# AFE_Supply.net
KiCad netlist of a schematic drawn in Altium Designer
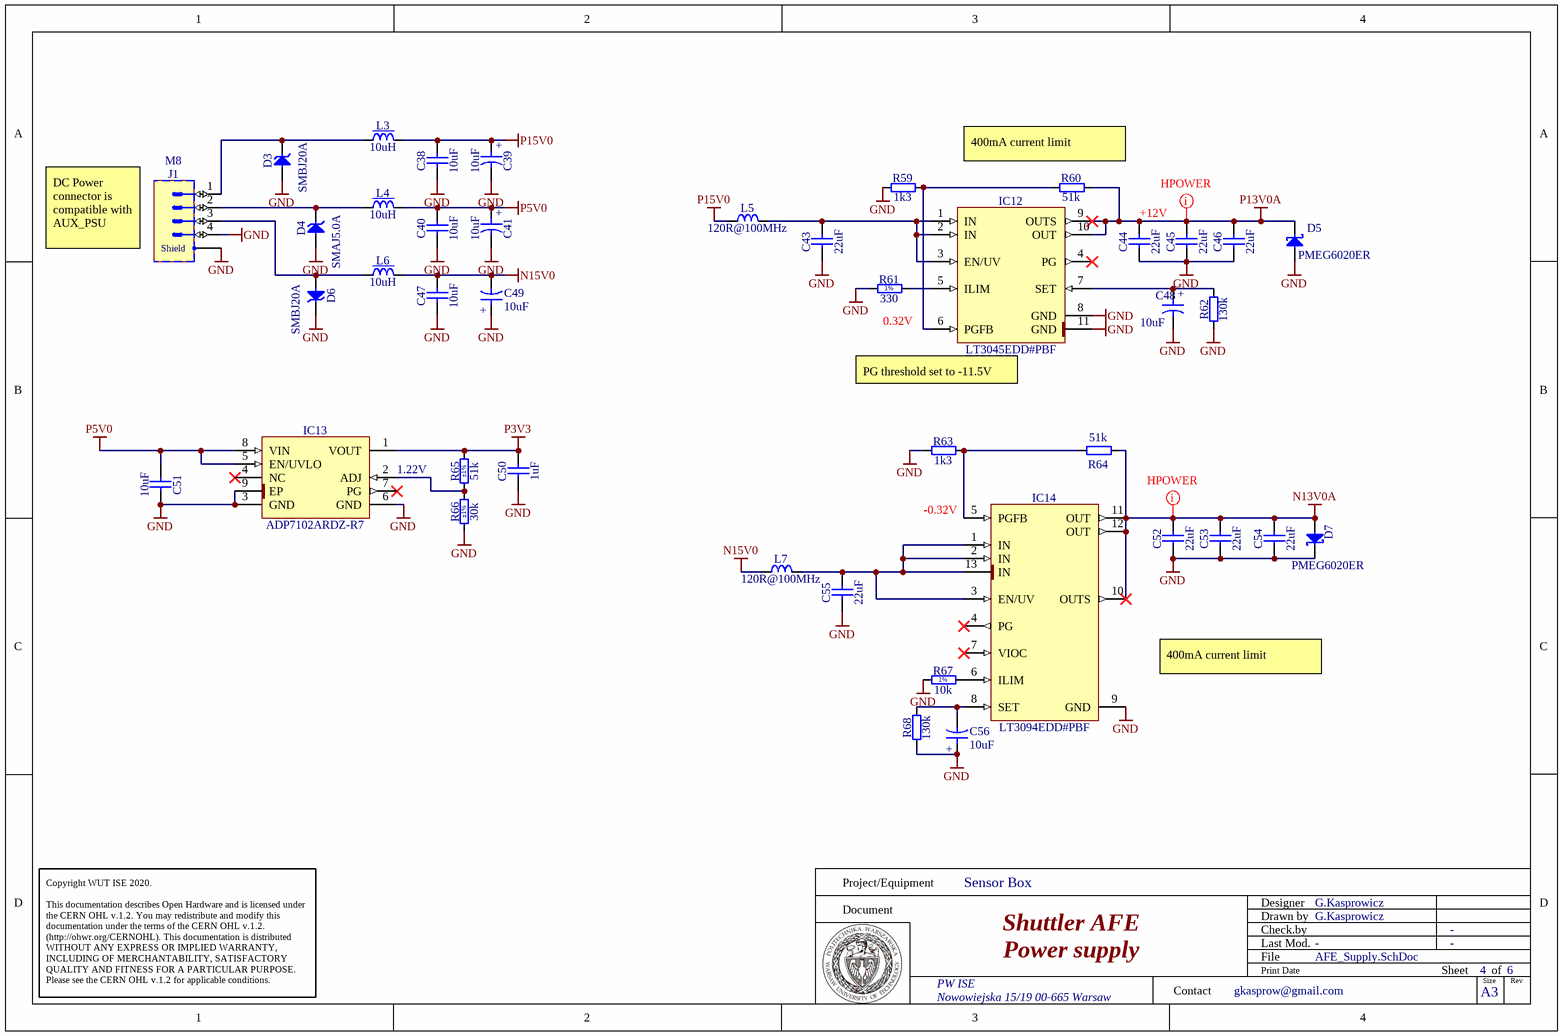
[diagram p0: AFE_Supply.SchDoc]

(export (version "E")
  (design (tool "Eeschema 10.0.6"))
  (components
    (comp (ref "C38")
      (value "10uF")
      (footprint "CAPC2012X95N")
      (description "Non-polarised capacitor")
      (fields
        (field (name "PART NUMBER") "CC0805_10UF_25V_10%_X5R")
        (field (name "VOLTAGE") "25V")
        (field (name "AUTHOR") "CERN DEM JLC")
      )
      (libsource (lib "Capacitors") (part "Capacitor - non polarized"))
    )
    (comp (ref "C39")
      (value "10uF")
      (footprint "CAPMP3216X180N")
      (description "Polarised capacitor")
      (fields
        (field (name "PART NUMBER") "CTE3216-18_10UF_16V_20%_AVX_TCJ")
        (field (name "VOLTAGE") "16V")
        (field (name "AUTHOR") "CERN DEM JLC")
      )
      (libsource (lib "Capacitors") (part "Capacitor - polarized"))
    )
    (comp (ref "C40")
      (value "10uF")
      (footprint "CAPC2012X95N")
      (description "Non-polarised capacitor")
      (fields
        (field (name "PART NUMBER") "CC0805_10UF_25V_10%_X5R")
        (field (name "VOLTAGE") "25V")
        (field (name "AUTHOR") "CERN DEM JLC")
      )
      (libsource (lib "Capacitors") (part "Capacitor - non polarized"))
    )
    (comp (ref "C41")
      (value "10uF")
      (footprint "CAPMP3216X180N")
      (description "Polarised capacitor")
      (fields
        (field (name "PART NUMBER") "CTE3216-18_10UF_16V_20%_AVX_TCJ")
        (field (name "VOLTAGE") "16V")
        (field (name "AUTHOR") "CERN DEM JLC")
      )
      (libsource (lib "Capacitors") (part "Capacitor - polarized"))
    )
    (comp (ref "C43")
      (value "22uF")
      (footprint "CAPC2012X135N")
      (description "Non-polarised capacitor")
      (fields
        (field (name "PART NUMBER") "CC0805_22UF_16V_10%_X5R")
        (field (name "VOLTAGE") "16V")
        (field (name "AUTHOR") "CERN DEM JLC")
      )
      (libsource (lib "Capacitors") (part "Capacitor - non polarized"))
    )
    (comp (ref "C44")
      (value "22uF")
      (footprint "CAPC2012X135N")
      (description "Non-polarised capacitor")
      (fields
        (field (name "PART NUMBER") "CC0805_22UF_16V_10%_X5R")
        (field (name "VOLTAGE") "16V")
        (field (name "AUTHOR") "CERN DEM JLC")
      )
      (libsource (lib "Capacitors") (part "Capacitor - non polarized"))
    )
    (comp (ref "C45")
      (value "22uF")
      (footprint "CAPC2012X135N")
      (description "Non-polarised capacitor")
      (fields
        (field (name "PART NUMBER") "CC0805_22UF_16V_10%_X5R")
        (field (name "VOLTAGE") "16V")
        (field (name "AUTHOR") "CERN DEM JLC")
      )
      (libsource (lib "Capacitors") (part "Capacitor - non polarized"))
    )
    (comp (ref "C46")
      (value "22uF")
      (footprint "CAPC2012X135N")
      (description "Non-polarised capacitor")
      (fields
        (field (name "PART NUMBER") "CC0805_22UF_16V_10%_X5R")
        (field (name "VOLTAGE") "16V")
        (field (name "AUTHOR") "CERN DEM JLC")
      )
      (libsource (lib "Capacitors") (part "Capacitor - non polarized"))
    )
    (comp (ref "C47")
      (value "10uF")
      (footprint "CAPC2012X95N")
      (description "Non-polarised capacitor")
      (fields
        (field (name "PART NUMBER") "CC0805_10UF_25V_10%_X5R")
        (field (name "VOLTAGE") "25V")
        (field (name "AUTHOR") "CERN DEM JLC")
      )
      (libsource (lib "Capacitors") (part "Capacitor - non polarized"))
    )
    (comp (ref "C48")
      (value "10uF")
      (footprint "CAPMP3216X180N")
      (description "Polarised capacitor")
      (fields
        (field (name "PART NUMBER") "CTE3216-18_10UF_16V_20%_AVX_TCJ")
        (field (name "VOLTAGE") "16V")
        (field (name "AUTHOR") "CERN DEM JLC")
      )
      (libsource (lib "Capacitors") (part "Capacitor - polarized"))
    )
    (comp (ref "C49")
      (value "10uF")
      (footprint "CAPMP3216X180N")
      (description "Polarised capacitor")
      (fields
        (field (name "PART NUMBER") "CTE3216-18_10UF_16V_20%_AVX_TCJ")
        (field (name "VOLTAGE") "16V")
        (field (name "AUTHOR") "CERN DEM JLC")
      )
      (libsource (lib "Capacitors") (part "Capacitor - polarized"))
    )
    (comp (ref "C50")
      (value "1uF")
      (footprint "CAPC1608X87N")
      (description "Non-polarised capacitor")
      (fields
        (field (name "PART NUMBER") "CC0603_1UF_25V_10%_X7R")
        (field (name "VOLTAGE") "25V")
        (field (name "AUTHOR") "CERN DEM JLC")
      )
      (libsource (lib "Capacitors") (part "Capacitor - non polarized"))
    )
    (comp (ref "C51")
      (value "10uF")
      (footprint "CAPC2012X135N")
      (description "Non-polarised capacitor")
      (fields
        (field (name "PART NUMBER") "CC0805_10UF_16V_10%_X5R")
        (field (name "VOLTAGE") "16V")
        (field (name "AUTHOR") "CERN DEM JLC")
      )
      (libsource (lib "Capacitors") (part "Capacitor - non polarized"))
    )
    (comp (ref "C52")
      (value "22uF")
      (footprint "CAPC2012X135N")
      (description "Non-polarised capacitor")
      (fields
        (field (name "PART NUMBER") "CC0805_22UF_16V_10%_X5R")
        (field (name "VOLTAGE") "16V")
        (field (name "AUTHOR") "CERN DEM JLC")
      )
      (libsource (lib "Capacitors") (part "Capacitor - non polarized"))
    )
    (comp (ref "C53")
      (value "22uF")
      (footprint "CAPC2012X135N")
      (description "Non-polarised capacitor")
      (fields
        (field (name "PART NUMBER") "CC0805_22UF_16V_10%_X5R")
        (field (name "VOLTAGE") "16V")
        (field (name "AUTHOR") "CERN DEM JLC")
      )
      (libsource (lib "Capacitors") (part "Capacitor - non polarized"))
    )
    (comp (ref "C54")
      (value "22uF")
      (footprint "CAPC2012X135N")
      (description "Non-polarised capacitor")
      (fields
        (field (name "PART NUMBER") "CC0805_22UF_16V_10%_X5R")
        (field (name "VOLTAGE") "16V")
        (field (name "AUTHOR") "CERN DEM JLC")
      )
      (libsource (lib "Capacitors") (part "Capacitor - non polarized"))
    )
    (comp (ref "C55")
      (value "22uF")
      (footprint "CAPC2012X135N")
      (description "Non-polarised capacitor")
      (fields
        (field (name "PART NUMBER") "CC0805_22UF_16V_10%_X5R")
        (field (name "VOLTAGE") "16V")
        (field (name "AUTHOR") "CERN DEM JLC")
      )
      (libsource (lib "Capacitors") (part "Capacitor - non polarized"))
    )
    (comp (ref "C56")
      (value "10uF")
      (footprint "CAPMP3216X180N")
      (description "Polarised capacitor")
      (fields
        (field (name "PART NUMBER") "CTE3216-18_10UF_16V_20%_AVX_TCJ")
        (field (name "VOLTAGE") "16V")
        (field (name "AUTHOR") "CERN DEM JLC")
      )
      (libsource (lib "Capacitors") (part "Capacitor - polarized"))
    )
    (comp (ref "D3")
      (value "SMBJ20A")
      (footprint "DIOM5336X265N")
      (description "Transient Voltage Suppressor Diode (Uni-Directional)")
      (fields
        (field (name "VOLTAGE") "20V")
        (field (name "POWER") "600W")
        (field (name "AUTHOR") "CERN DEM JLC")
      )
      (libsource (lib "ICs And Semiconductors") (part "Diode TVS Uni-Directional"))
    )
    (comp (ref "D4")
      (value "SMAJ5.0A")
      (footprint "DIOM5226X262N")
      (description "Transient Voltage Suppressor Diode (Uni-Directional)")
      (fields
        (field (name "VOLTAGE") "5V")
        (field (name "POWER") "400W")
        (field (name "AUTHOR") "CERN DEM MR")
      )
      (libsource (lib "ICs And Semiconductors") (part "Diode TVS Uni-Directional"))
    )
    (comp (ref "D5")
      (value "PMEG6020ER")
      (footprint "SODFL3517X110N")
      (description "Schottky Diode")
      (fields
        (field (name "VOLTAGE") "60V")
        (field (name "POWER") "2A")
        (field (name "AUTHOR") "CERN DEM JMW")
      )
      (libsource (lib "ICs And Semiconductors") (part "Diode Schottky"))
    )
    (comp (ref "D6")
      (value "SMBJ20A")
      (footprint "DIOM5336X265N")
      (description "Transient Voltage Suppressor Diode (Uni-Directional)")
      (fields
        (field (name "VOLTAGE") "20V")
        (field (name "POWER") "600W")
        (field (name "AUTHOR") "CERN DEM JLC")
      )
      (libsource (lib "ICs And Semiconductors") (part "Diode TVS Uni-Directional"))
    )
    (comp (ref "D7")
      (value "PMEG6020ER")
      (footprint "SODFL3517X110N")
      (description "Schottky Diode")
      (fields
        (field (name "VOLTAGE") "60V")
        (field (name "POWER") "2A")
        (field (name "AUTHOR") "CERN DEM JMW")
      )
      (libsource (lib "ICs And Semiconductors") (part "Diode Schottky"))
    )
    (comp (ref "IC12")
      (value "LT3045EDD#PBF")
      (footprint "SON50P300X300X80-11N-R175X248")
      (description "20V, 500mA, Ultralow Noise, Ultrahigh PSRR Linear Regulator")
      (fields (field (name "MANUFACTURER") "LINEAR TECHNOLOGY") (field (name "AUTHOR") "CERN DEM JLC"))
      (libsource (lib "ICs And Semiconductors") (part "LT3045EDD"))
    )
    (comp (ref "IC13")
      (value "ADP7102ARDZ-R7")
      (footprint "SOIC127P600X175-9N-R241X309")
      (description "1.22V to 19V, 300mA, Low Noise, CMOS LDO Adjustable Linear Regulator")
      (fields (field (name "MANUFACTURER") "ANALOG DEVICES") (field (name "AUTHOR") "CERN DEM JLC"))
      (libsource (lib "ICs And Semiconductors") (part "ADP7102ARDZ-R7"))
    )
    (comp (ref "IC14")
      (value "LT3094EDD#PBF")
      (footprint "SON45P300X300X80-13N-R175X248")
      (description "-20V, 500mA, Ultralow Noise, Ultrahigh PSRR Negative Linear Regulator")
      (fields (field (name "MANUFACTURER") "LINEAR TECHNOLOGY") (field (name "AUTHOR") "CERN DEM JLC"))
      (libsource (lib "ICs And Semiconductors") (part "LT3094"))
    )
    (comp (ref "J1")
      (value "M8")
      (footprint "AMPHENOL_M8AS-04PMMR-SF8001")
      (description "Connector 4 Male + Shield")
      (fields
        (field (name "PART NUMBER") "AMPHENOL_M8AS-04PMMR-SF8001")
        (field (name "MANUFACTURER") "AMPHENOL")
        (field (name "AUTHOR") "CERN DEM MR")
      )
      (libsource (lib "Connectors") (part "Connector 4 Male + Shield"))
    )
    (comp (ref "L3")
      (value "10uH")
      (footprint "IND_MURATA_LQW32FT_0H")
      (description "Inductor With Core")
      (fields
        (field (name "PART NUMBER") "IND1210_10UH_20%_MURATA_LQW32FT100M0H")
        (field (name "POWER") "500mA")
        (field (name "AUTHOR") "CERN DEM BC")
      )
      (libsource (lib "Inductors & Transformers") (part "Inductor With Magnetic core"))
    )
    (comp (ref "L4")
      (value "10uH")
      (footprint "IND_MURATA_LQW32FT_0H")
      (description "Inductor With Core")
      (fields
        (field (name "PART NUMBER") "IND1210_10UH_20%_MURATA_LQW32FT100M0H")
        (field (name "POWER") "500mA")
        (field (name "AUTHOR") "CERN DEM BC")
      )
      (libsource (lib "Inductors & Transformers") (part "Inductor With Magnetic core"))
    )
    (comp (ref "L5")
      (value "120R@100MHz")
      (footprint "INDC1608X95N")
      (description "Inductor")
      (fields
        (field (name "PART NUMBER") "IND0603_MURATA_BLM18PG121SN1D")
        (field (name "POWER") "2A")
        (field (name "AUTHOR") "CERN DEM BC")
      )
      (libsource (lib "Inductors & Transformers") (part "Inductor"))
    )
    (comp (ref "L6")
      (value "10uH")
      (footprint "IND_MURATA_LQW32FT_0H")
      (description "Inductor With Core")
      (fields
        (field (name "PART NUMBER") "IND1210_10UH_20%_MURATA_LQW32FT100M0H")
        (field (name "POWER") "500mA")
        (field (name "AUTHOR") "CERN DEM BC")
      )
      (libsource (lib "Inductors & Transformers") (part "Inductor With Magnetic core"))
    )
    (comp (ref "L7")
      (value "120R@100MHz")
      (footprint "INDC1608X95N")
      (description "Inductor")
      (fields
        (field (name "PART NUMBER") "IND0603_MURATA_BLM18PG121SN1D")
        (field (name "POWER") "2A")
        (field (name "AUTHOR") "CERN DEM BC")
      )
      (libsource (lib "Inductors & Transformers") (part "Inductor"))
    )
    (comp (ref "R59")
      (value "1k3")
      (footprint "RESC1005X40N")
      (description "Resistor - 1%")
      (fields
        (field (name "PART NUMBER") "R0402_1K3_1%_0.0625W_100PPM")
        (field (name "POWER") "0.0625W")
        (field (name "AUTHOR") "CERN DEM JLC")
      )
      (libsource (lib "Resistors") (part "Resistor - 1%"))
    )
    (comp (ref "R60")
      (value "51k")
      (footprint "RESC1005X40N")
      (description "Resistor - 1%")
      (fields
        (field (name "PART NUMBER") "R0402_51K_1%_0.0625W_100PPM")
        (field (name "POWER") "0.0625W")
        (field (name "AUTHOR") "CERN DEM JLC")
      )
      (libsource (lib "Resistors") (part "Resistor - 1%"))
    )
    (comp (ref "R61")
      (value "330")
      (footprint "RESC1005X40N")
      (description "Resistor - 1%")
      (fields
        (field (name "PART NUMBER") "R0402_330R_1%_0.0625W_100PPM")
        (field (name "POWER") "0.0625W")
        (field (name "AUTHOR") "CERN DEM JLC")
      )
      (libsource (lib "") (part "Resistor - 1%_1"))
    )
    (comp (ref "R62")
      (value "130k")
      (footprint "RESC1608X55N")
      (description "Resistor - 1%")
      (fields
        (field (name "PART NUMBER") "R0603_130K_1%_0.1W_100PPM")
        (field (name "POWER") "0.1W")
        (field (name "AUTHOR") "CERN DEM JLC")
      )
      (libsource (lib "Resistors") (part "Resistor - 1%"))
    )
    (comp (ref "R63")
      (value "1k3")
      (footprint "RESC1005X40N")
      (description "Resistor - 1%")
      (fields
        (field (name "PART NUMBER") "R0402_1K3_1%_0.0625W_100PPM")
        (field (name "POWER") "0.0625W")
        (field (name "AUTHOR") "CERN DEM JLC")
      )
      (libsource (lib "Resistors") (part "Resistor - 1%"))
    )
    (comp (ref "R64")
      (value "51k")
      (footprint "RESC1005X40N")
      (description "Resistor - 1%")
      (fields
        (field (name "PART NUMBER") "R0402_51K_1%_0.0625W_100PPM")
        (field (name "POWER") "0.0625W")
        (field (name "AUTHOR") "CERN DEM JLC")
      )
      (libsource (lib "Resistors") (part "Resistor - 1%"))
    )
    (comp (ref "R65")
      (value "51k")
      (footprint "RESC1005X40N")
      (description "Resistor - 1%")
      (fields
        (field (name "TOLERANCE") "±1%")
        (field (name "PART NUMBER") "R0402_51K_1%_0.0625W_100PPM")
        (field (name "POWER") "0.0625W")
        (field (name "AUTHOR") "CERN DEM JLC")
      )
      (libsource (lib "Resistors") (part "Resistor - 1%"))
    )
    (comp (ref "R66")
      (value "30k")
      (footprint "RESC1005X40N")
      (description "Resistor - 1%")
      (fields
        (field (name "TOLERANCE") "±1%")
        (field (name "PART NUMBER") "R0402_30K_1%_0.0625W_100PPM")
        (field (name "POWER") "0.0625W")
        (field (name "AUTHOR") "CERN DEM JLC")
      )
      (libsource (lib "Resistors") (part "Resistor - 1%"))
    )
    (comp (ref "R67")
      (value "10k")
      (footprint "RESC1005X40N")
      (description "Resistor - 1%")
      (fields
        (field (name "PART NUMBER") "R0402_10K_1%_0.0625W_100PPM")
        (field (name "POWER") "0.0625W")
        (field (name "AUTHOR") "CERN DEM JLC")
      )
      (libsource (lib "") (part "Resistor - 1%_1"))
    )
    (comp (ref "R68")
      (value "130k")
      (footprint "RESC1608X55N")
      (description "Resistor - 1%")
      (fields
        (field (name "PART NUMBER") "R0603_130K_1%_0.1W_100PPM")
        (field (name "POWER") "0.1W")
        (field (name "AUTHOR") "CERN DEM JLC")
      )
      (libsource (lib "Resistors") (part "Resistor - 1%"))
    )
  )
  (nets
    (net (code "1") (name "GND") (class "Default")
      (node (ref "C38") (pin "1") (pinfunction "1_1") (pintype "passive"))
      (node (ref "C39") (pin "2") (pinfunction "2_2") (pintype "passive"))
      (node (ref "C40") (pin "1") (pinfunction "1_1") (pintype "passive"))
      (node (ref "C41") (pin "2") (pinfunction "2_2") (pintype "passive"))
      (node (ref "C43") (pin "1") (pinfunction "1_1") (pintype "passive"))
      (node (ref "C44") (pin "1") (pinfunction "1_1") (pintype "passive"))
      (node (ref "C45") (pin "1") (pinfunction "1_1") (pintype "passive"))
      (node (ref "C46") (pin "1") (pinfunction "1_1") (pintype "passive"))
      (node (ref "C47") (pin "1") (pinfunction "1_1") (pintype "passive"))
      (node (ref "C48") (pin "2") (pinfunction "2_2") (pintype "passive"))
      (node (ref "C49") (pin "1") (pinfunction "1_1") (pintype "passive"))
      (node (ref "C50") (pin "1") (pinfunction "1_1") (pintype "passive"))
      (node (ref "C51") (pin "2") (pinfunction "2_2") (pintype "passive"))
      (node (ref "C52") (pin "1") (pinfunction "1_1") (pintype "passive"))
      (node (ref "C53") (pin "1") (pinfunction "1_1") (pintype "passive"))
      (node (ref "C54") (pin "1") (pinfunction "1_1") (pintype "passive"))
      (node (ref "C55") (pin "1") (pinfunction "1_1") (pintype "passive"))
      (node (ref "C56") (pin "1") (pinfunction "1_1") (pintype "passive"))
      (node (ref "D3") (pin "2") (pinfunction "A_2") (pintype "passive"))
      (node (ref "D4") (pin "2") (pinfunction "A_2") (pintype "passive"))
      (node (ref "D5") (pin "2") (pinfunction "A_2") (pintype "passive"))
      (node (ref "D6") (pin "1") (pinfunction "C_1") (pintype "passive"))
      (node (ref "D7") (pin "1") (pinfunction "C_1") (pintype "passive"))
      (node (ref "IC12") (pin "11") (pinfunction "GND_11") (pintype "power_in"))
      (node (ref "IC12") (pin "8") (pinfunction "GND_8") (pintype "power_in"))
      (node (ref "IC13") (pin "3") (pinfunction "GND_3") (pintype "power_in"))
      (node (ref "IC13") (pin "6") (pinfunction "GND_6") (pintype "power_in"))
      (node (ref "IC13") (pin "9") (pinfunction "EP_9") (pintype "power_in"))
      (node (ref "IC14") (pin "9") (pinfunction "GND_9") (pintype "power_in"))
      (node (ref "J1") (pin "4") (pinfunction "4_4") (pintype "bidirectional"))
      (node (ref "J1") (pin "SHIELD") (pinfunction "SHIELD_SHIELD") (pintype "passive"))
      (node (ref "R59") (pin "1") (pinfunction "1_1") (pintype "passive"))
      (node (ref "R61") (pin "1") (pinfunction "1_1") (pintype "passive"))
      (node (ref "R62") (pin "1") (pinfunction "1_1") (pintype "passive"))
      (node (ref "R63") (pin "1") (pinfunction "1_1") (pintype "passive"))
      (node (ref "R66") (pin "1") (pinfunction "1_1") (pintype "passive"))
      (node (ref "R67") (pin "1") (pinfunction "1_1") (pintype "passive"))
      (node (ref "R68") (pin "1") (pinfunction "1_1") (pintype "passive"))
    )
    (net (code "2") (name "N13V0A") (class "Default")
      (node (ref "C52") (pin "2") (pinfunction "2_2") (pintype "passive"))
      (node (ref "C53") (pin "2") (pinfunction "2_2") (pintype "passive"))
      (node (ref "C54") (pin "2") (pinfunction "2_2") (pintype "passive"))
      (node (ref "D7") (pin "2") (pinfunction "A_2") (pintype "passive"))
      (node (ref "IC14") (pin "10") (pinfunction "OUTS_10") (pintype "output"))
      (node (ref "IC14") (pin "11") (pinfunction "OUT_11") (pintype "output"))
      (node (ref "IC14") (pin "12") (pinfunction "OUT_12") (pintype "output"))
      (node (ref "R64") (pin "1") (pinfunction "1_1") (pintype "passive"))
    )
    (net (code "3") (name "N15V0") (class "Default")
      (node (ref "C47") (pin "2") (pinfunction "2_2") (pintype "passive"))
      (node (ref "C49") (pin "2") (pinfunction "2_2") (pintype "passive"))
      (node (ref "L6") (pin "2") (pinfunction "2_2") (pintype "passive"))
      (node (ref "L7") (pin "1") (pinfunction "1_1") (pintype "passive"))
    )
    (net (code "4") (name "Net-(D3-C)") (class "Default")
      (node (ref "D3") (pin "1") (pinfunction "C_1") (pintype "passive"))
      (node (ref "J1") (pin "1") (pinfunction "1_1") (pintype "bidirectional"))
      (node (ref "L3") (pin "1") (pinfunction "1_1") (pintype "passive"))
    )
    (net (code "5") (name "Net-(D4-C)") (class "Default")
      (node (ref "D4") (pin "1") (pinfunction "C_1") (pintype "passive"))
      (node (ref "J1") (pin "2") (pinfunction "2_2") (pintype "bidirectional"))
      (node (ref "L4") (pin "1") (pinfunction "1_1") (pintype "passive"))
    )
    (net (code "6") (name "Net-(D6-A)") (class "Default")
      (node (ref "D6") (pin "2") (pinfunction "A_2") (pintype "passive"))
      (node (ref "J1") (pin "3") (pinfunction "3_3") (pintype "bidirectional"))
      (node (ref "L6") (pin "1") (pinfunction "1_1") (pintype "passive"))
    )
    (net (code "7") (name "Net-(IC12-EN{slash}UV)") (class "Default")
      (node (ref "C43") (pin "2") (pinfunction "2_2") (pintype "passive"))
      (node (ref "IC12") (pin "1") (pinfunction "IN_1") (pintype "input"))
      (node (ref "IC12") (pin "2") (pinfunction "IN_2") (pintype "input"))
      (node (ref "IC12") (pin "3") (pinfunction "EN/UV_3") (pintype "input"))
      (node (ref "L5") (pin "2") (pinfunction "2_2") (pintype "passive"))
    )
    (net (code "8") (name "Net-(IC12-ILIM)") (class "Default")
      (node (ref "IC12") (pin "5") (pinfunction "ILIM_5") (pintype "input"))
      (node (ref "R61") (pin "2") (pinfunction "2_2") (pintype "passive"))
    )
    (net (code "9") (name "Net-(IC12-PGFB)") (class "Default")
      (node (ref "IC12") (pin "6") (pinfunction "PGFB_6") (pintype "input"))
      (node (ref "R59") (pin "2") (pinfunction "2_2") (pintype "passive"))
      (node (ref "R60") (pin "1") (pinfunction "1_1") (pintype "passive"))
    )
    (net (code "10") (name "Net-(IC12-SET)") (class "Default")
      (node (ref "C48") (pin "1") (pinfunction "1_1") (pintype "passive"))
      (node (ref "IC12") (pin "7") (pinfunction "SET_7") (pintype "input"))
      (node (ref "R62") (pin "2") (pinfunction "2_2") (pintype "passive"))
    )
    (net (code "11") (name "Net-(IC13-ADJ)") (class "Default")
      (node (ref "IC13") (pin "2") (pinfunction "ADJ_2") (pintype "input"))
      (node (ref "R65") (pin "1") (pinfunction "1_1") (pintype "passive"))
      (node (ref "R66") (pin "2") (pinfunction "2_2") (pintype "passive"))
    )
    (net (code "12") (name "Net-(IC14-EN{slash}UV)") (class "Default")
      (node (ref "C55") (pin "2") (pinfunction "2_2") (pintype "passive"))
      (node (ref "IC14") (pin "1") (pinfunction "IN_1") (pintype "input"))
      (node (ref "IC14") (pin "13") (pinfunction "IN_13") (pintype "power_in"))
      (node (ref "IC14") (pin "2") (pinfunction "IN_2") (pintype "input"))
      (node (ref "IC14") (pin "3") (pinfunction "EN/UV_3") (pintype "input"))
      (node (ref "L7") (pin "2") (pinfunction "2_2") (pintype "passive"))
    )
    (net (code "13") (name "Net-(IC14-ILIM)") (class "Default")
      (node (ref "IC14") (pin "6") (pinfunction "ILIM_6") (pintype "input"))
      (node (ref "R67") (pin "2") (pinfunction "2_2") (pintype "passive"))
    )
    (net (code "14") (name "Net-(IC14-PGFB)") (class "Default")
      (node (ref "IC14") (pin "5") (pinfunction "PGFB_5") (pintype "input"))
      (node (ref "R63") (pin "2") (pinfunction "2_2") (pintype "passive"))
      (node (ref "R64") (pin "2") (pinfunction "2_2") (pintype "passive"))
    )
    (net (code "15") (name "Net-(IC14-SET)") (class "Default")
      (node (ref "C56") (pin "2") (pinfunction "2_2") (pintype "passive"))
      (node (ref "IC14") (pin "8") (pinfunction "SET_8") (pintype "input"))
      (node (ref "R68") (pin "2") (pinfunction "2_2") (pintype "passive"))
    )
    (net (code "16") (name "P3V3") (class "Default")
      (node (ref "C50") (pin "2") (pinfunction "2_2") (pintype "passive"))
      (node (ref "IC13") (pin "1") (pinfunction "VOUT_1") (pintype "power_in"))
      (node (ref "R65") (pin "2") (pinfunction "2_2") (pintype "passive"))
    )
    (net (code "17") (name "P5V0") (class "Default")
      (node (ref "C40") (pin "2") (pinfunction "2_2") (pintype "passive"))
      (node (ref "C41") (pin "1") (pinfunction "1_1") (pintype "passive"))
      (node (ref "C51") (pin "1") (pinfunction "1_1") (pintype "passive"))
      (node (ref "IC13") (pin "5") (pinfunction "EN/UVLO_5") (pintype "input"))
      (node (ref "IC13") (pin "8") (pinfunction "VIN_8") (pintype "input"))
      (node (ref "L4") (pin "2") (pinfunction "2_2") (pintype "passive"))
    )
    (net (code "18") (name "P13V0A") (class "Default")
      (node (ref "C44") (pin "2") (pinfunction "2_2") (pintype "passive"))
      (node (ref "C45") (pin "2") (pinfunction "2_2") (pintype "passive"))
      (node (ref "C46") (pin "2") (pinfunction "2_2") (pintype "passive"))
      (node (ref "D5") (pin "1") (pinfunction "C_1") (pintype "passive"))
      (node (ref "IC12") (pin "10") (pinfunction "OUT_10") (pintype "output"))
      (node (ref "IC12") (pin "9") (pinfunction "OUTS_9") (pintype "output"))
      (node (ref "R60") (pin "2") (pinfunction "2_2") (pintype "passive"))
    )
    (net (code "19") (name "P15V0") (class "Default")
      (node (ref "C38") (pin "2") (pinfunction "2_2") (pintype "passive"))
      (node (ref "C39") (pin "1") (pinfunction "1_1") (pintype "passive"))
      (node (ref "L3") (pin "2") (pinfunction "2_2") (pintype "passive"))
      (node (ref "L5") (pin "1") (pinfunction "1_1") (pintype "passive"))
    )
    (net (code "20") (name "unconnected-(IC12-PG-Pad4)") (class "Default")
      (node (ref "IC12") (pin "4") (pinfunction "PG_4") (pintype "output+no_connect"))
    )
    (net (code "21") (name "unconnected-(IC13-NC-Pad4)") (class "Default")
      (node (ref "IC13") (pin "4") (pinfunction "NC_4") (pintype "passive+no_connect"))
    )
    (net (code "22") (name "unconnected-(IC13-PG-Pad7)") (class "Default")
      (node (ref "IC13") (pin "7") (pinfunction "PG_7") (pintype "output+no_connect"))
    )
    (net (code "23") (name "unconnected-(IC14-PG-Pad4)") (class "Default")
      (node (ref "IC14") (pin "4") (pinfunction "PG_4") (pintype "output+no_connect"))
    )
    (net (code "24") (name "unconnected-(IC14-VIOC-Pad7)") (class "Default")
      (node (ref "IC14") (pin "7") (pinfunction "VIOC_7") (pintype "input+no_connect"))
    )
  )
)
